# RC_Switch.net
KiCad netlist of a schematic drawn in EAGLE
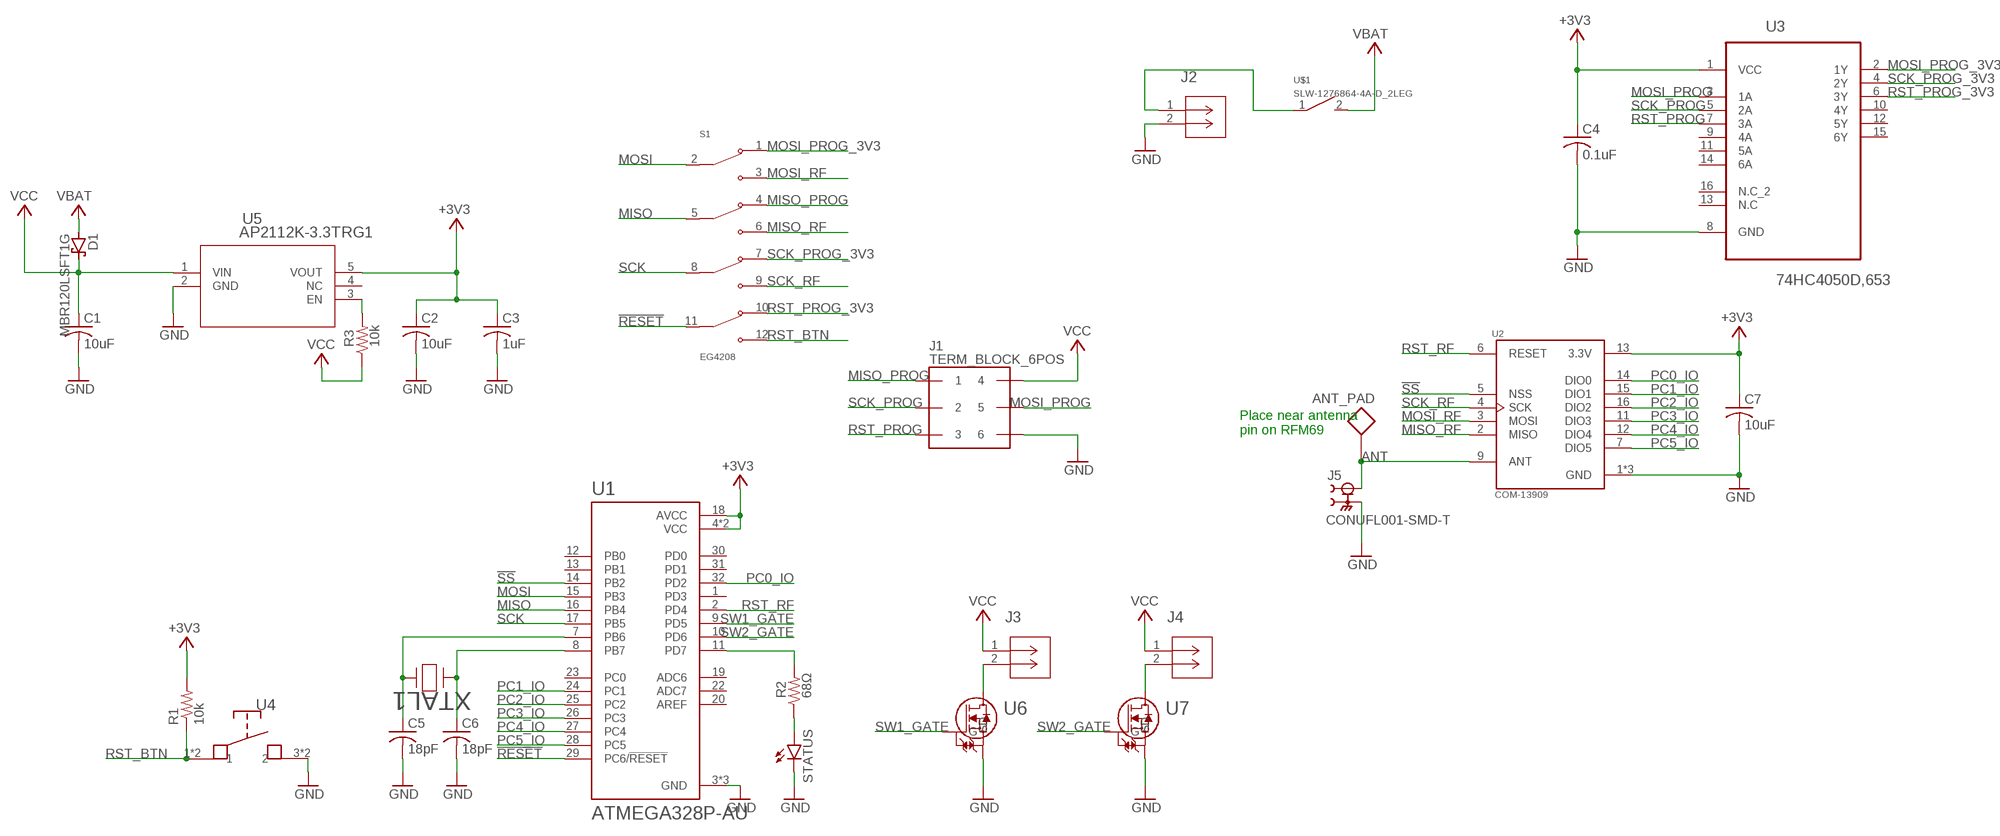
[diagram p0: schematic, sheet 1]

(export (version "E")
  (design (tool "Eeschema 10.0.6"))
  (components
    (comp (ref "ANT_PAD")
      (value "CIRCLE_PAD_40MIL")
      (footprint "eagle-import:CIRCLE_PAD_40MIL")
      (libsource (lib "eagle-import") (part "CIRCLE_PAD_40MIL"))
    )
    (comp (ref "C1")
      (value "10uF")
      (footprint "eagle-import:C1206")
      (libsource (lib "eagle-import") (part "C-USC1206"))
    )
    (comp (ref "C2")
      (value "10uF")
      (footprint "eagle-import:C1206")
      (libsource (lib "eagle-import") (part "C-USC1206"))
    )
    (comp (ref "C3")
      (value "1uF")
      (footprint "eagle-import:C1206")
      (libsource (lib "eagle-import") (part "C-USC1206"))
    )
    (comp (ref "C4")
      (value "0.1uF")
      (footprint "eagle-import:C1206")
      (libsource (lib "eagle-import") (part "C-USC1206"))
    )
    (comp (ref "C5")
      (value "18pF")
      (footprint "eagle-import:C1206")
      (libsource (lib "eagle-import") (part "C-USC1206"))
    )
    (comp (ref "C6")
      (value "18pF")
      (footprint "eagle-import:C1206")
      (libsource (lib "eagle-import") (part "C-USC1206"))
    )
    (comp (ref "C7")
      (value "10uF")
      (footprint "eagle-import:C1206")
      (libsource (lib "eagle-import") (part "C-USC1206"))
    )
    (comp (ref "D1")
      (value "MBR120LSFT1G")
      (footprint "eagle-import:DIOM3616X98N")
      (libsource (lib "eagle-import") (part "MBR120LSFT1G"))
    )
    (comp (ref "J1")
      (value "TERM_BLOCK_6POS")
      (footprint "eagle-import:TERM_BLOCK_6POS")
      (libsource (lib "eagle-import") (part "TERM_BLOCK_6POS"))
    )
    (comp (ref "J2")
      (value "S2B-PH-K-S(LF)(SN)")
      (footprint "eagle-import:CONN_S2B-PH-K-S_JST")
      (fields (field (name "COPYRIGHT") "Copyright (C) 2024 Ultra Librarian. All rights reserved."))
      (libsource (lib "eagle-import") (part "S2B-PH-K-S(LF)(SN)"))
    )
    (comp (ref "J3")
      (value "691137710002")
      (footprint "eagle-import:CONN2_710002_WRE")
      (fields (field (name "COPYRIGHT") "Copyright (C) 2024 Ultra Librarian. All rights reserved."))
      (libsource (lib "eagle-import") (part "691137710002"))
    )
    (comp (ref "J4")
      (value "691137710002")
      (footprint "eagle-import:CONN2_710002_WRE")
      (fields (field (name "COPYRIGHT") "Copyright (C) 2024 Ultra Librarian. All rights reserved."))
      (libsource (lib "eagle-import") (part "691137710002"))
    )
    (comp (ref "J5")
      (value "CONUFL001-SMD-T")
      (footprint "eagle-import:LINX_CONUFL001-SMD-T")
      (fields (field (name "MF") "Linx Technologies"))
      (libsource (lib "eagle-import") (part "CONUFL001-SMD-T"))
    )
    (comp (ref "R1")
      (value "10k")
      (footprint "eagle-import:R1206")
      (libsource (lib "eagle-import") (part "R-US_R1206"))
    )
    (comp (ref "R2")
      (value "68Ω")
      (footprint "eagle-import:R1206")
      (libsource (lib "eagle-import") (part "R-US_R1206"))
    )
    (comp (ref "R3")
      (value "10k")
      (footprint "eagle-import:R1206")
      (libsource (lib "eagle-import") (part "R-US_R1206"))
    )
    (comp (ref "S1")
      (value "EG4208")
      (footprint "eagle-import:SW_EG4208")
      (fields (field (name "MF") "E-Switch"))
      (libsource (lib "eagle-import") (part "EG4208"))
    )
    (comp (ref "STATUS")
      (value "LEDCHIPLED_1206")
      (footprint "eagle-import:CHIPLED_1206")
      (libsource (lib "eagle-import") (part "LEDCHIPLED_1206"))
    )
    (comp (ref "U$1")
      (value "SLW-1276864-4A-D_2LEG")
      (footprint "eagle-import:SLW-1276864-4A-D_2LEG")
      (libsource (lib "eagle-import") (part "SLW-1276864-4A-D_2LEG"))
    )
    (comp (ref "U1")
      (value "ATMEGA328P-AU")
      (footprint "eagle-import:QFP80P900X900X120-32N")
      (fields (field (name "MF") "Microchip"))
      (libsource (lib "eagle-import") (part "ATMEGA328P-AU"))
    )
    (comp (ref "U2")
      (value "COM-13909")
      (footprint "eagle-import:MOD_COM-13909")
      (fields (field (name "MF") "SparkFun Electronics"))
      (libsource (lib "eagle-import") (part "COM-13909"))
    )
    (comp (ref "U3")
      (value "74HC4050D,653")
      (footprint "eagle-import:SOIC127P600X175-16N")
      (fields (field (name "MF") "Nexperia USA Inc."))
      (libsource (lib "eagle-import") (part "74HC4050D,653"))
    )
    (comp (ref "U4")
      (value "PTS526_SK15_SMTR2_LFS")
      (footprint "eagle-import:SMT_FS")
      (fields
        (field (name "MANUFACTURER_PART_NUMBER") "PTS526 SK15 SMTR2 LFS")
        (field (name "COPYRIGHT") "Copyright (C) 2024 Ultra Librarian. All rights reserved.")
      )
      (libsource (lib "eagle-import") (part "PTS526_SK15_SMTR2_LFS"))
    )
    (comp (ref "U5")
      (value "AP2112K-3.3TRG1")
      (footprint "eagle-import:SOT_RG1_DIO")
      (fields (field (name "COPYRIGHT") "Copyright (C) 2024 Ultra Librarian. All rights reserved."))
      (libsource (lib "eagle-import") (part "AP2112K-3.3TRG1"))
    )
    (comp (ref "U6")
      (value "DMN3023L-7")
      (footprint "eagle-import:SOT-23_2P9X1P3_DIO")
      (fields (field (name "COPYRIGHT") "Copyright (C) 2024 Ultra Librarian. All rights reserved."))
      (libsource (lib "eagle-import") (part "DMN3023L-7"))
    )
    (comp (ref "U7")
      (value "DMN3023L-7")
      (footprint "eagle-import:SOT-23_2P9X1P3_DIO")
      (fields (field (name "COPYRIGHT") "Copyright (C) 2024 Ultra Librarian. All rights reserved."))
      (libsource (lib "eagle-import") (part "DMN3023L-7"))
    )
    (comp (ref "XTAL1")
      (value "ABLS-8.000MHZ-B4-T")
      (footprint "eagle-import:XTAL_ABLS2_ABR")
      (fields (field (name "COPYRIGHT") "Copyright (C) 2024 Ultra Librarian. All rights reserved."))
      (libsource (lib "eagle-import") (part "ABLS-8.000MHZ-B4-T"))
    )
  )
  (nets
    (net (code "1") (name "+3V3") (class "Default")
      (node (ref "C2") (pin "1") (pinfunction "1_1") (pintype "passive"))
      (node (ref "C3") (pin "1") (pinfunction "1_1") (pintype "passive"))
      (node (ref "C4") (pin "1") (pinfunction "1_1") (pintype "passive"))
      (node (ref "C7") (pin "1") (pinfunction "1_1") (pintype "passive"))
      (node (ref "R1") (pin "2") (pinfunction "2_2") (pintype "passive"))
      (node (ref "U1") (pin "18") (pinfunction "AVCC_18") (pintype "power_in"))
      (node (ref "U1") (pin "4") (pinfunction "VCC_4") (pintype "power_in"))
      (node (ref "U1") (pin "6") (pinfunction "VCC_6") (pintype "power_in"))
      (node (ref "U2") (pin "13") (pinfunction "3.3V_13") (pintype "power_in"))
      (node (ref "U3") (pin "1") (pinfunction "VCC_1") (pintype "power_in"))
      (node (ref "U5") (pin "5") (pinfunction "VOUT_5") (pintype "passive"))
    )
    (net (code "2") (name "/ANT") (class "Default")
      (node (ref "ANT_PAD") (pin "P$1") (pinfunction "P$1_P$1") (pintype "passive"))
      (node (ref "J5") (pin "1") (pinfunction "1_1") (pintype "passive"))
      (node (ref "U2") (pin "9") (pinfunction "ANT_9") (pintype "bidirectional"))
    )
    (net (code "3") (name "/MISO") (class "Default")
      (node (ref "S1") (pin "5") (pinfunction "COM2_5") (pintype "passive"))
      (node (ref "U1") (pin "16") (pinfunction "PB4_16") (pintype "bidirectional"))
    )
    (net (code "4") (name "/MISO_PROG") (class "Default")
      (node (ref "J1") (pin "1") (pinfunction "1_1") (pintype "bidirectional"))
      (node (ref "S1") (pin "4") (pinfunction "NC2_4") (pintype "passive"))
    )
    (net (code "5") (name "/MISO_RF") (class "Default")
      (node (ref "S1") (pin "6") (pinfunction "NO2_6") (pintype "passive"))
      (node (ref "U2") (pin "2") (pinfunction "MISO_2") (pintype "input"))
    )
    (net (code "6") (name "/MOSI") (class "Default")
      (node (ref "S1") (pin "2") (pinfunction "COM1_2") (pintype "passive"))
      (node (ref "U1") (pin "15") (pinfunction "PB3_15") (pintype "bidirectional"))
    )
    (net (code "7") (name "/MOSI_PROG") (class "Default")
      (node (ref "J1") (pin "5") (pinfunction "5_5") (pintype "bidirectional"))
      (node (ref "U3") (pin "3") (pinfunction "1A_3") (pintype "input"))
    )
    (net (code "8") (name "/MOSI_PROG_3V3") (class "Default")
      (node (ref "S1") (pin "1") (pinfunction "NC1_1") (pintype "passive"))
      (node (ref "U3") (pin "2") (pinfunction "1Y_2") (pintype "output"))
    )
    (net (code "9") (name "/MOSI_RF") (class "Default")
      (node (ref "S1") (pin "3") (pinfunction "NO1_3") (pintype "passive"))
      (node (ref "U2") (pin "3") (pinfunction "MOSI_3") (pintype "output"))
    )
    (net (code "10") (name "/PC0_IO") (class "Default")
      (node (ref "U1") (pin "32") (pinfunction "PD2_32") (pintype "bidirectional"))
      (node (ref "U2") (pin "14") (pinfunction "DIO0_14") (pintype "bidirectional"))
    )
    (net (code "11") (name "/PC1_IO") (class "Default")
      (node (ref "U1") (pin "24") (pinfunction "PC1_24") (pintype "bidirectional"))
      (node (ref "U2") (pin "15") (pinfunction "DIO1_15") (pintype "bidirectional"))
    )
    (net (code "12") (name "/PC2_IO") (class "Default")
      (node (ref "U1") (pin "25") (pinfunction "PC2_25") (pintype "bidirectional"))
      (node (ref "U2") (pin "16") (pinfunction "DIO2_16") (pintype "bidirectional"))
    )
    (net (code "13") (name "/PC3_IO") (class "Default")
      (node (ref "U1") (pin "26") (pinfunction "PC3_26") (pintype "bidirectional"))
      (node (ref "U2") (pin "11") (pinfunction "DIO3_11") (pintype "bidirectional"))
    )
    (net (code "14") (name "/PC4_IO") (class "Default")
      (node (ref "U1") (pin "27") (pinfunction "PC4_27") (pintype "bidirectional"))
      (node (ref "U2") (pin "12") (pinfunction "DIO4_12") (pintype "bidirectional"))
    )
    (net (code "15") (name "/PC5_IO") (class "Default")
      (node (ref "U1") (pin "28") (pinfunction "PC5_28") (pintype "bidirectional"))
      (node (ref "U2") (pin "7") (pinfunction "DIO5_7") (pintype "bidirectional"))
    )
    (net (code "16") (name "/RST_BTN") (class "Default")
      (node (ref "R1") (pin "1") (pinfunction "1_1") (pintype "passive"))
      (node (ref "S1") (pin "12") (pinfunction "NO4_12") (pintype "passive"))
      (node (ref "U4") (pin "1") (pinfunction "1_1") (pintype "passive"))
      (node (ref "U4") (pin "2") (pinfunction "1_2") (pintype "passive"))
    )
    (net (code "17") (name "/RST_PROG") (class "Default")
      (node (ref "J1") (pin "3") (pinfunction "3_3") (pintype "bidirectional"))
      (node (ref "U3") (pin "7") (pinfunction "3A_7") (pintype "input"))
    )
    (net (code "18") (name "/RST_PROG_3V3") (class "Default")
      (node (ref "S1") (pin "10") (pinfunction "NC4_10") (pintype "passive"))
      (node (ref "U3") (pin "6") (pinfunction "3Y_6") (pintype "output"))
    )
    (net (code "19") (name "/RST_RF") (class "Default")
      (node (ref "U1") (pin "2") (pinfunction "PD4_2") (pintype "bidirectional"))
      (node (ref "U2") (pin "6") (pinfunction "RESET_6") (pintype "bidirectional"))
    )
    (net (code "20") (name "/SCK") (class "Default")
      (node (ref "S1") (pin "8") (pinfunction "COM3_8") (pintype "passive"))
      (node (ref "U1") (pin "17") (pinfunction "PB5_17") (pintype "bidirectional"))
    )
    (net (code "21") (name "/SCK_PROG") (class "Default")
      (node (ref "J1") (pin "2") (pinfunction "2_2") (pintype "bidirectional"))
      (node (ref "U3") (pin "5") (pinfunction "2A_5") (pintype "input"))
    )
    (net (code "22") (name "/SCK_PROG_3V3") (class "Default")
      (node (ref "S1") (pin "7") (pinfunction "NC3_7") (pintype "passive"))
      (node (ref "U3") (pin "4") (pinfunction "2Y_4") (pintype "output"))
    )
    (net (code "23") (name "/SCK_RF") (class "Default")
      (node (ref "S1") (pin "9") (pinfunction "NO3_9") (pintype "passive"))
      (node (ref "U2") (pin "4") (pinfunction "SCK_4") (pintype "input"))
    )
    (net (code "24") (name "/SW1_GATE") (class "Default")
      (node (ref "U1") (pin "9") (pinfunction "PD5_9") (pintype "bidirectional"))
      (node (ref "U6") (pin "1") (pinfunction "G_1") (pintype "passive"))
    )
    (net (code "25") (name "/SW2_GATE") (class "Default")
      (node (ref "U1") (pin "10") (pinfunction "PD6_10") (pintype "bidirectional"))
      (node (ref "U7") (pin "1") (pinfunction "G_1") (pintype "passive"))
    )
    (net (code "26") (name "/~{RESET}") (class "Default")
      (node (ref "S1") (pin "11") (pinfunction "COM4_11") (pintype "passive"))
      (node (ref "U1") (pin "29") (pinfunction "PC6/~{RESET}_29") (pintype "bidirectional"))
    )
    (net (code "27") (name "/~{SS}") (class "Default")
      (node (ref "U1") (pin "14") (pinfunction "PB2_14") (pintype "bidirectional"))
      (node (ref "U2") (pin "5") (pinfunction "NSS_5") (pintype "input"))
    )
    (net (code "28") (name "GND") (class "Default")
      (node (ref "C1") (pin "2") (pinfunction "2_2") (pintype "passive"))
      (node (ref "C2") (pin "2") (pinfunction "2_2") (pintype "passive"))
      (node (ref "C3") (pin "2") (pinfunction "2_2") (pintype "passive"))
      (node (ref "C4") (pin "2") (pinfunction "2_2") (pintype "passive"))
      (node (ref "C5") (pin "2") (pinfunction "2_2") (pintype "passive"))
      (node (ref "C6") (pin "2") (pinfunction "2_2") (pintype "passive"))
      (node (ref "C7") (pin "2") (pinfunction "2_2") (pintype "passive"))
      (node (ref "J1") (pin "6") (pinfunction "6_6") (pintype "bidirectional"))
      (node (ref "J2") (pin "2") (pinfunction "2_2") (pintype "passive"))
      (node (ref "J5") (pin "2") (pinfunction "2_2") (pintype "passive"))
      (node (ref "J5") (pin "3") (pinfunction "2_3") (pintype "passive"))
      (node (ref "STATUS") (pin "C") (pinfunction "C_C") (pintype "passive"))
      (node (ref "U1") (pin "21") (pinfunction "GND_21") (pintype "power_in"))
      (node (ref "U1") (pin "3") (pinfunction "GND_3") (pintype "power_in"))
      (node (ref "U1") (pin "5") (pinfunction "GND_5") (pintype "power_in"))
      (node (ref "U2") (pin "1") (pinfunction "GND_1") (pintype "power_in"))
      (node (ref "U2") (pin "10") (pinfunction "GND_10") (pintype "power_in"))
      (node (ref "U2") (pin "8") (pinfunction "GND_8") (pintype "power_in"))
      (node (ref "U3") (pin "8") (pinfunction "GND_8") (pintype "passive"))
      (node (ref "U4") (pin "3") (pinfunction "2_3") (pintype "passive"))
      (node (ref "U4") (pin "4") (pinfunction "2_4") (pintype "passive"))
      (node (ref "U5") (pin "2") (pinfunction "GND_2") (pintype "passive"))
      (node (ref "U6") (pin "2") (pinfunction "S_2") (pintype "power_in"))
      (node (ref "U7") (pin "2") (pinfunction "S_2") (pintype "power_in"))
    )
    (net (code "29") (name "Net-(R2-Pad1)") (class "Default")
      (node (ref "R2") (pin "1") (pinfunction "1_1") (pintype "passive"))
      (node (ref "STATUS") (pin "A") (pinfunction "A_A") (pintype "passive"))
    )
    (net (code "30") (name "Net-(U$1-P$1)") (class "Default")
      (node (ref "J2") (pin "1") (pinfunction "1_1") (pintype "passive"))
      (node (ref "U$1") (pin "1") (pinfunction "P$1_1") (pintype "bidirectional"))
    )
    (net (code "31") (name "Net-(U1-PB6)") (class "Default")
      (node (ref "C5") (pin "1") (pinfunction "1_1") (pintype "passive"))
      (node (ref "U1") (pin "7") (pinfunction "PB6_7") (pintype "bidirectional"))
      (node (ref "XTAL1") (pin "2") (pinfunction "2_2") (pintype "passive"))
    )
    (net (code "32") (name "Net-(U1-PB7)") (class "Default")
      (node (ref "C6") (pin "1") (pinfunction "1_1") (pintype "passive"))
      (node (ref "U1") (pin "8") (pinfunction "PB7_8") (pintype "bidirectional"))
      (node (ref "XTAL1") (pin "1") (pinfunction "1_1") (pintype "passive"))
    )
    (net (code "33") (name "Net-(U1-PD7)") (class "Default")
      (node (ref "R2") (pin "2") (pinfunction "2_2") (pintype "passive"))
      (node (ref "U1") (pin "11") (pinfunction "PD7_11") (pintype "bidirectional"))
    )
    (net (code "34") (name "Net-(U5-EN)") (class "Default")
      (node (ref "R3") (pin "2") (pinfunction "2_2") (pintype "passive"))
      (node (ref "U5") (pin "3") (pinfunction "EN_3") (pintype "passive"))
    )
    (net (code "35") (name "Net-(U6-D)") (class "Default")
      (node (ref "J3") (pin "2") (pinfunction "2_2") (pintype "passive"))
      (node (ref "U6") (pin "3") (pinfunction "D_3") (pintype "passive"))
    )
    (net (code "36") (name "Net-(U7-D)") (class "Default")
      (node (ref "J4") (pin "2") (pinfunction "2_2") (pintype "passive"))
      (node (ref "U7") (pin "3") (pinfunction "D_3") (pintype "passive"))
    )
    (net (code "37") (name "VBAT") (class "Default")
      (node (ref "D1") (pin "2") (pinfunction "A_2") (pintype "passive"))
      (node (ref "U$1") (pin "2") (pinfunction "P$2_2") (pintype "bidirectional"))
    )
    (net (code "38") (name "VCC") (class "Default")
      (node (ref "C1") (pin "1") (pinfunction "1_1") (pintype "passive"))
      (node (ref "D1") (pin "1") (pinfunction "C_1") (pintype "passive"))
      (node (ref "J1") (pin "4") (pinfunction "4_4") (pintype "bidirectional"))
      (node (ref "J3") (pin "1") (pinfunction "1_1") (pintype "passive"))
      (node (ref "J4") (pin "1") (pinfunction "1_1") (pintype "passive"))
      (node (ref "R3") (pin "1") (pinfunction "1_1") (pintype "passive"))
      (node (ref "U5") (pin "1") (pinfunction "VIN_1") (pintype "passive"))
    )
    (net (code "39") (name "unconnected-(U1-ADC6-Pad19)") (class "Default")
      (node (ref "U1") (pin "19") (pinfunction "ADC6_19") (pintype "bidirectional"))
    )
    (net (code "40") (name "unconnected-(U1-ADC7-Pad22)") (class "Default")
      (node (ref "U1") (pin "22") (pinfunction "ADC7_22") (pintype "bidirectional"))
    )
    (net (code "41") (name "unconnected-(U1-AREF-Pad20)") (class "Default")
      (node (ref "U1") (pin "20") (pinfunction "AREF_20") (pintype "input"))
    )
    (net (code "42") (name "unconnected-(U1-PB0-Pad12)") (class "Default")
      (node (ref "U1") (pin "12") (pinfunction "PB0_12") (pintype "bidirectional"))
    )
    (net (code "43") (name "unconnected-(U1-PB1-Pad13)") (class "Default")
      (node (ref "U1") (pin "13") (pinfunction "PB1_13") (pintype "bidirectional"))
    )
    (net (code "44") (name "unconnected-(U1-PC0-Pad23)") (class "Default")
      (node (ref "U1") (pin "23") (pinfunction "PC0_23") (pintype "bidirectional"))
    )
    (net (code "45") (name "unconnected-(U1-PD0-Pad30)") (class "Default")
      (node (ref "U1") (pin "30") (pinfunction "PD0_30") (pintype "bidirectional"))
    )
    (net (code "46") (name "unconnected-(U1-PD1-Pad31)") (class "Default")
      (node (ref "U1") (pin "31") (pinfunction "PD1_31") (pintype "bidirectional"))
    )
    (net (code "47") (name "unconnected-(U1-PD3-Pad1)") (class "Default")
      (node (ref "U1") (pin "1") (pinfunction "PD3_1") (pintype "bidirectional"))
    )
    (net (code "48") (name "unconnected-(U3-4A-Pad9)") (class "Default")
      (node (ref "U3") (pin "9") (pinfunction "4A_9") (pintype "input"))
    )
    (net (code "49") (name "unconnected-(U3-4Y-Pad10)") (class "Default")
      (node (ref "U3") (pin "10") (pinfunction "4Y_10") (pintype "output"))
    )
    (net (code "50") (name "unconnected-(U3-5A-Pad11)") (class "Default")
      (node (ref "U3") (pin "11") (pinfunction "5A_11") (pintype "input"))
    )
    (net (code "51") (name "unconnected-(U3-5Y-Pad12)") (class "Default")
      (node (ref "U3") (pin "12") (pinfunction "5Y_12") (pintype "output"))
    )
    (net (code "52") (name "unconnected-(U3-6A-Pad14)") (class "Default")
      (node (ref "U3") (pin "14") (pinfunction "6A_14") (pintype "input"))
    )
    (net (code "53") (name "unconnected-(U3-6Y-Pad15)") (class "Default")
      (node (ref "U3") (pin "15") (pinfunction "6Y_15") (pintype "output"))
    )
    (net (code "54") (name "unconnected-(U3-N.C-Pad13)") (class "Default")
      (node (ref "U3") (pin "13") (pinfunction "N.C_13") (pintype "no_connect"))
    )
    (net (code "55") (name "unconnected-(U3-N.C_2-Pad16)") (class "Default")
      (node (ref "U3") (pin "16") (pinfunction "N.C_2_16") (pintype "no_connect"))
    )
    (net (code "56") (name "unconnected-(U5-NC-Pad4)") (class "Default")
      (node (ref "U5") (pin "4") (pinfunction "NC_4") (pintype "passive"))
    )
  )
)
